# pwr.net
KiCad netlist of a schematic drawn in Altium Designer
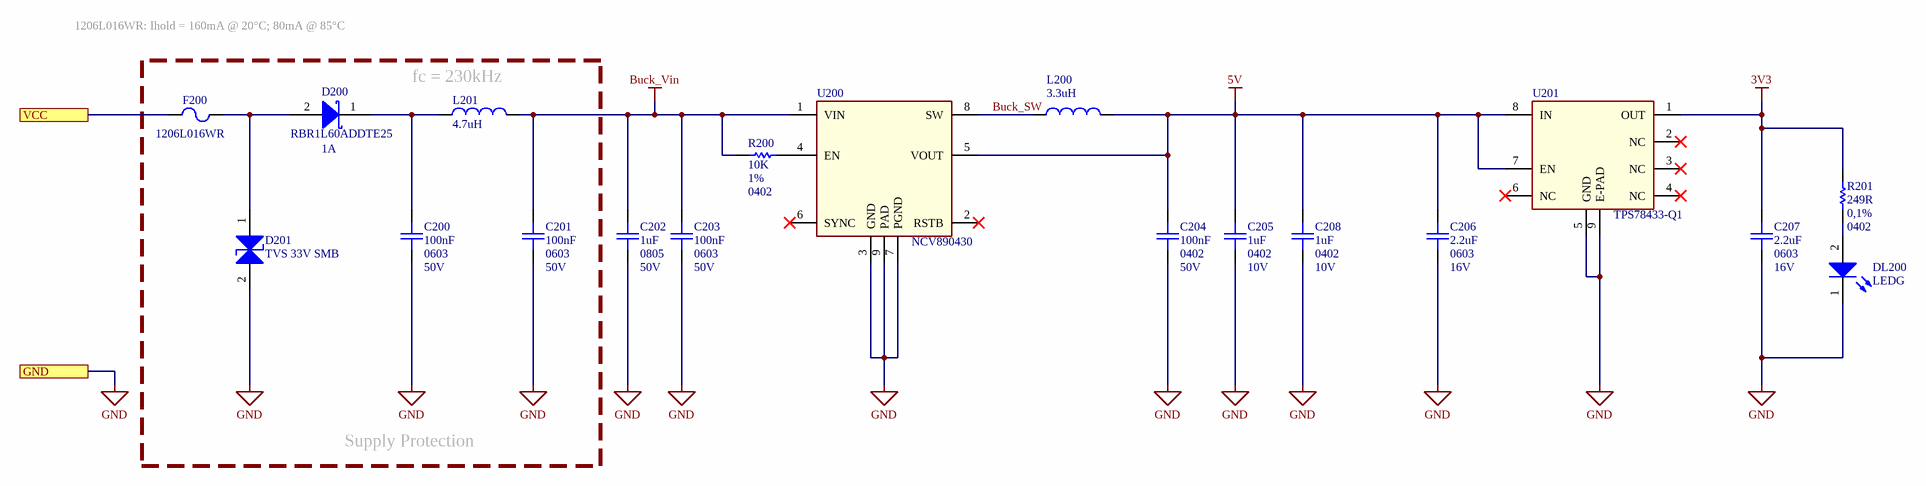
[diagram p0: pwr.SchDoc]

(export (version "E")
  (design (tool "Eeschema 10.0.6"))
  (components
    (comp (ref "C200")
      (value "100nF")
      (footprint "CER0603")
      (description "MLCC Automotive, 100nF, 0603, 50V, 10%, X8L")
      (fields
        (field (name "CASE/PACKAGE") "0603")
        (field (name "OP VOLTAGE") "50V")
        (field (name "TOLERANCE") "10%")
      )
      (libsource (lib "PMP_CapsDB") (part "CapCer_SMD_2"))
    )
    (comp (ref "C201")
      (value "100nF")
      (footprint "CER0603")
      (description "MLCC Automotive, 100nF, 0603, 50V, 10%, X8L")
      (fields
        (field (name "CASE/PACKAGE") "0603")
        (field (name "OP VOLTAGE") "50V")
        (field (name "TOLERANCE") "10%")
      )
      (libsource (lib "PMP_CapsDB") (part "CapCer_SMD_2"))
    )
    (comp (ref "C202")
      (value "1uF")
      (footprint "CER0805")
      (description "MLCC Automotive, 1uF, 0805, 50V, 10%, X7R")
      (fields
        (field (name "CASE/PACKAGE") "0805")
        (field (name "OP VOLTAGE") "50V")
        (field (name "TOLERANCE") "10%")
      )
      (libsource (lib "PMP_CapsDB") (part "CapCer_SMD_2"))
    )
    (comp (ref "C203")
      (value "100nF")
      (footprint "CER0603")
      (description "MLCC Automotive, 100nF, 0603, 50V, 10%, X8L")
      (fields
        (field (name "CASE/PACKAGE") "0603")
        (field (name "OP VOLTAGE") "50V")
        (field (name "TOLERANCE") "10%")
      )
      (libsource (lib "PMP_CapsDB") (part "CapCer_SMD_2"))
    )
    (comp (ref "C204")
      (value "100nF")
      (footprint "CER0402")
      (description "MLCC Automotive, 100nF, 0402, 50V, 10%, X7r")
      (fields
        (field (name "CASE/PACKAGE") "0402")
        (field (name "OP VOLTAGE") "50V")
        (field (name "TOLERANCE") "10%")
      )
      (libsource (lib "PMP_CapsDB") (part "CapCer_SMD_2"))
    )
    (comp (ref "C205")
      (value "1uF")
      (footprint "CER0402")
      (description "MLCC Automotive, 1uF, 0402, 10V, 20%, X7S")
      (fields
        (field (name "CASE/PACKAGE") "0402")
        (field (name "OP VOLTAGE") "10V")
        (field (name "TOLERANCE") "20.00%")
      )
      (libsource (lib "PMP_CapsDB") (part "CapCer_SMD_2"))
    )
    (comp (ref "C206")
      (value "2.2uF")
      (footprint "CER0603")
      (description "MLCC Automotive, 2.2uF, 0603, 16V, 10%, X7S")
      (fields
        (field (name "CASE/PACKAGE") "0603")
        (field (name "OP VOLTAGE") "16V")
        (field (name "TOLERANCE") "10%")
      )
      (libsource (lib "PMP_CapsDB") (part "CapCer_SMD_2"))
    )
    (comp (ref "C207")
      (value "2.2uF")
      (footprint "CER0603")
      (description "MLCC Automotive, 2.2uF, 0603, 16V, 10%, X7S")
      (fields
        (field (name "CASE/PACKAGE") "0603")
        (field (name "OP VOLTAGE") "16V")
        (field (name "TOLERANCE") "10%")
      )
      (libsource (lib "PMP_CapsDB") (part "CapCer_SMD_2"))
    )
    (comp (ref "C208")
      (value "1uF")
      (footprint "CER0402")
      (description "MLCC Automotive, 1uF, 0402, 10V, 20%, X7S")
      (fields
        (field (name "CASE/PACKAGE") "0402")
        (field (name "OP VOLTAGE") "10V")
        (field (name "TOLERANCE") "20.00%")
      )
      (libsource (lib "PMP_CapsDB") (part "CapCer_SMD_2"))
    )
    (comp (ref "D200")
      (value "RBR1L60ADDTE25")
      (footprint "DO-214AC_SMA")
      (description "Schottky Rectifier Diode 1A 60V SMA")
      (fields (field (name "IF (A)") "1A") (field (name "Comment") "Shottky Rect Diode SMD"))
      (libsource (lib "Pmp_DiscretesDB") (part "Diode_SMD_2_Schottky"))
    )
    (comp (ref "D201")
      (value "TVS 33V SMB")
      (footprint "DO-214AA_SMB")
      (description "TVS Bidir 33V SMB")
      (fields (field (name "Comment") "SMD/PTH TVS Bidirectional Diode"))
      (libsource (lib "Pmp_DiscretesDB") (part "TVS_2_Bidirectional"))
    )
    (comp (ref "DL200")
      (value "LEDG")
      (footprint "LED SMD 0603")
      (description "LED standard - SMD Grn 560nm 6.3mcd 2.2 V, 20mA, 0603 AECQ-102")
      (fields (field (name "Comment") "Single Color SMD LED"))
      (libsource (lib "Pmp_OptoDB") (part "LED_SMD_2_Single"))
    )
    (comp (ref "F200")
      (value "1206L016WR")
      (footprint "FUSC3216X125N")
      (description "Resettable Fuse PPTC, 160mA Hold, 370mA Trip, 4.5R min, 30V")
      (fields (field (name "Comment") "Fuse_PTCRes"))
      (libsource (lib "PMP_CirProtection") (part "FuseRes"))
    )
    (comp (ref "L200")
      (value "3.3uH")
      (footprint "WE-MAPI_1212")
      (description "Power Inductors - SMD WE-MAPI 3,3uH 1.1A DCR=266mOhms AECQ200")
      (fields (field (name "Comment") "SMD Inductor"))
      (libsource (lib "PMP_MagneticsDB") (part "Ind_SMD_2"))
    )
    (comp (ref "L201")
      (value "4.7uH")
      (footprint "WE-LQ_1210")
      (description "EMI Filtering Inductor WE-LQ SMT, 4.7uH, 490mA,")
      (fields (field (name "Comment") "SMD Inductor"))
      (libsource (lib "PMP_MagneticsDB") (part "Ind_SMD_2"))
    )
    (comp (ref "R200")
      (value "10K")
      (footprint "Res0402")
      (description "Thick Film SM Chip Resistors, 10K, 0402, ±1%, 1/10W")
      (fields
        (field (name "TOLERANCE") "1%")
        (field (name "CASE/PACKAGE") "0402")
        (field (name "POWER") "63mW")
        (field (name "Comment") "SMD Resistor")
      )
      (libsource (lib "PMP_ResDB") (part "Res_SMD_2"))
    )
    (comp (ref "R201")
      (value "249R")
      (footprint "Res0402")
      (description "Thick Film SM Chip Resistors, 249R, 0402, ±0.1%, 10ppm 1/16W")
      (fields
        (field (name "TOLERANCE") "0,1%")
        (field (name "CASE/PACKAGE") "0402")
        (field (name "POWER") "63mW")
        (field (name "Comment") "SMD Resistor")
      )
      (libsource (lib "PMP_ResDB") (part "Res_SMD_2"))
    )
    (comp (ref "U200")
      (value "NCV890430")
      (footprint "SON65P300X300X100-9N")
      (description "synchronous buck converter; 3.5-37Vin; 5Vout; 600mA")
      (fields (field (name "Comment") "ONSEMI_NCV890430"))
      (libsource (lib "PMP_ICsDB") (part "ONSEMI_NCV890430"))
    )
    (comp (ref "U201")
      (value "TPS78433-Q1")
      (footprint "SON65P300X100_HS-9N_NOPAD")
      (description "TPS784-Q1 Automotive, 3.3V, 300mA, High-PSRR LDO")
      (fields (field (name "Comment") "TI_TPS78533Q_VSON"))
      (libsource (lib "PMP_ICsDB") (part "TI_TPS78533Q_VSON"))
    )
  )
  (nets
    (net (code "1") (name "/Buck_SW") (class "Default")
      (node (ref "L200") (pin "1") (pinfunction "1_1") (pintype "passive"))
      (node (ref "U200") (pin "8") (pinfunction "SW_8") (pintype "passive"))
    )
    (net (code "2") (name "/VCC") (class "Default")
      (node (ref "F200") (pin "1") (pinfunction "1_1") (pintype "passive"))
    )
    (net (code "3") (name "3V3") (class "Default")
      (node (ref "C207") (pin "1") (pinfunction "1_1") (pintype "passive"))
      (node (ref "R201") (pin "2") (pinfunction "2_2") (pintype "passive"))
      (node (ref "U201") (pin "1") (pinfunction "OUT_1") (pintype "power_in"))
    )
    (net (code "4") (name "5V") (class "Default")
      (node (ref "C204") (pin "1") (pinfunction "1_1") (pintype "passive"))
      (node (ref "C205") (pin "1") (pinfunction "1_1") (pintype "passive"))
      (node (ref "C206") (pin "1") (pinfunction "1_1") (pintype "passive"))
      (node (ref "C208") (pin "1") (pinfunction "1_1") (pintype "passive"))
      (node (ref "L200") (pin "2") (pinfunction "2_2") (pintype "passive"))
      (node (ref "U200") (pin "5") (pinfunction "VOUT_5") (pintype "passive"))
      (node (ref "U201") (pin "7") (pinfunction "EN_7") (pintype "passive"))
      (node (ref "U201") (pin "8") (pinfunction "IN_8") (pintype "power_in"))
    )
    (net (code "5") (name "Buck_Vin") (class "Default")
      (node (ref "C201") (pin "1") (pinfunction "1_1") (pintype "passive"))
      (node (ref "C202") (pin "1") (pinfunction "1_1") (pintype "passive"))
      (node (ref "C203") (pin "1") (pinfunction "1_1") (pintype "passive"))
      (node (ref "L201") (pin "2") (pinfunction "2_2") (pintype "passive"))
      (node (ref "R200") (pin "2") (pinfunction "2_2") (pintype "passive"))
      (node (ref "U200") (pin "1") (pinfunction "VIN_1") (pintype "passive"))
    )
    (net (code "6") (name "GND") (class "Default")
      (node (ref "C200") (pin "2") (pinfunction "2_2") (pintype "passive"))
      (node (ref "C201") (pin "2") (pinfunction "2_2") (pintype "passive"))
      (node (ref "C202") (pin "2") (pinfunction "2_2") (pintype "passive"))
      (node (ref "C203") (pin "2") (pinfunction "2_2") (pintype "passive"))
      (node (ref "C204") (pin "2") (pinfunction "2_2") (pintype "passive"))
      (node (ref "C205") (pin "2") (pinfunction "2_2") (pintype "passive"))
      (node (ref "C206") (pin "2") (pinfunction "2_2") (pintype "passive"))
      (node (ref "C207") (pin "2") (pinfunction "2_2") (pintype "passive"))
      (node (ref "C208") (pin "2") (pinfunction "2_2") (pintype "passive"))
      (node (ref "D201") (pin "2") (pinfunction "K_2") (pintype "passive"))
      (node (ref "DL200") (pin "1") (pinfunction "K_1") (pintype "passive"))
      (node (ref "U200") (pin "3") (pinfunction "GND_3") (pintype "passive"))
      (node (ref "U200") (pin "7") (pinfunction "PGND_7") (pintype "passive"))
      (node (ref "U200") (pin "9") (pinfunction "PAD_9") (pintype "passive"))
      (node (ref "U201") (pin "5") (pinfunction "GND_5") (pintype "power_in"))
      (node (ref "U201") (pin "9") (pinfunction "E-PAD_9") (pintype "passive"))
    )
    (net (code "7") (name "Net-(D200-A)") (class "Default")
      (node (ref "D200") (pin "2") (pinfunction "A_2") (pintype "passive"))
      (node (ref "D201") (pin "1") (pinfunction "A_1") (pintype "passive"))
      (node (ref "F200") (pin "2") (pinfunction "2_2") (pintype "passive"))
    )
    (net (code "8") (name "Net-(D200-K)") (class "Default")
      (node (ref "C200") (pin "1") (pinfunction "1_1") (pintype "passive"))
      (node (ref "D200") (pin "1") (pinfunction "K_1") (pintype "passive"))
      (node (ref "L201") (pin "1") (pinfunction "1_1") (pintype "passive"))
    )
    (net (code "9") (name "Net-(DL200-A)") (class "Default")
      (node (ref "DL200") (pin "2") (pinfunction "A_2") (pintype "passive"))
      (node (ref "R201") (pin "1") (pinfunction "1_1") (pintype "passive"))
    )
    (net (code "10") (name "Net-(U200-EN)") (class "Default")
      (node (ref "R200") (pin "1") (pinfunction "1_1") (pintype "passive"))
      (node (ref "U200") (pin "4") (pinfunction "EN_4") (pintype "passive"))
    )
    (net (code "11") (name "unconnected-(U200-RSTB-Pad2)") (class "Default")
      (node (ref "U200") (pin "2") (pinfunction "RSTB_2") (pintype "passive+no_connect"))
    )
    (net (code "12") (name "unconnected-(U200-SYNC-Pad6)") (class "Default")
      (node (ref "U200") (pin "6") (pinfunction "SYNC_6") (pintype "passive+no_connect"))
    )
    (net (code "13") (name "unconnected-(U201-NC-Pad2)") (class "Default")
      (node (ref "U201") (pin "2") (pinfunction "NC_2") (pintype "passive+no_connect"))
    )
    (net (code "14") (name "unconnected-(U201-NC-Pad3)") (class "Default")
      (node (ref "U201") (pin "3") (pinfunction "NC_3") (pintype "passive+no_connect"))
    )
    (net (code "15") (name "unconnected-(U201-NC-Pad4)") (class "Default")
      (node (ref "U201") (pin "4") (pinfunction "NC_4") (pintype "passive+no_connect"))
    )
    (net (code "16") (name "unconnected-(U201-NC-Pad6)") (class "Default")
      (node (ref "U201") (pin "6") (pinfunction "NC_6") (pintype "passive+no_connect"))
    )
  )
)
